# ArduinoLFO_Main.net
KiCad netlist of a schematic drawn in EAGLE
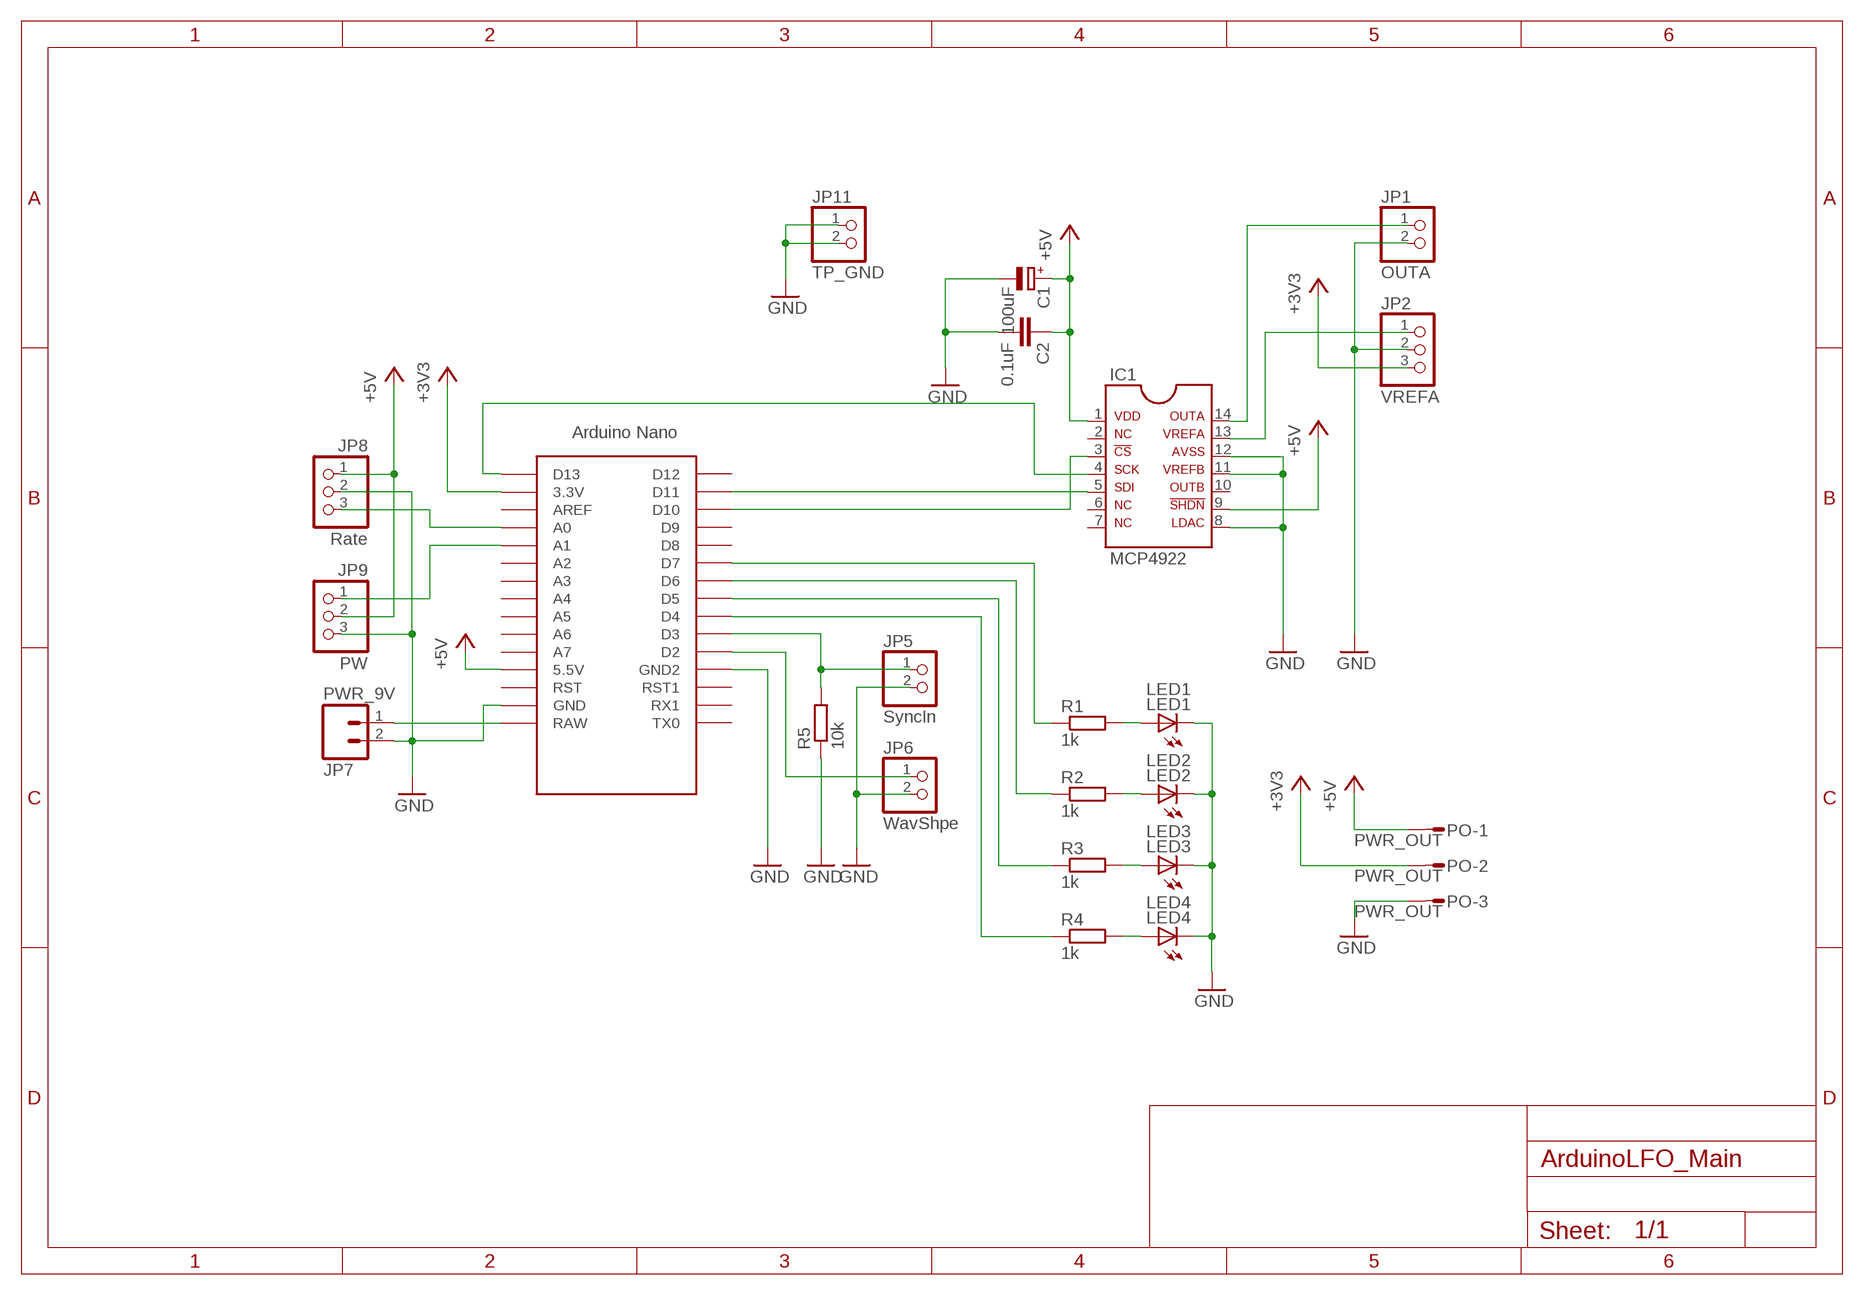
[diagram p0: schematic, sheet 1]

(export (version "E")
  (design (tool "Eeschema 10.0.6"))
  (components
    (comp (ref "C1")
      (value "100uF")
      (footprint "eagle-import:E2,5-7")
      (libsource (lib "eagle-import") (part "CPOL-EUE2.5-7"))
    )
    (comp (ref "C2")
      (value "0.1uF")
      (footprint "eagle-import:C025-024X044")
      (libsource (lib "eagle-import") (part "C-EU025-024X044"))
    )
    (comp (ref "IC1")
      (value "MCP4922")
      (footprint "eagle-import:MCP4922")
      (libsource (lib "eagle-import") (part "MCP4922"))
    )
    (comp (ref "JP1")
      (value "OUTA")
      (footprint "eagle-import:1X02")
      (libsource (lib "eagle-import") (part "PINHD-1X2"))
    )
    (comp (ref "JP2")
      (value "VREFA")
      (footprint "eagle-import:1X03")
      (libsource (lib "eagle-import") (part "PINHD-1X3"))
    )
    (comp (ref "JP5")
      (value "SyncIn")
      (footprint "eagle-import:1X02")
      (libsource (lib "eagle-import") (part "PINHD-1X2"))
    )
    (comp (ref "JP6")
      (value "WavShpe")
      (footprint "eagle-import:1X02")
      (libsource (lib "eagle-import") (part "PINHD-1X2"))
    )
    (comp (ref "JP7")
      (value "PWR_9V")
      (footprint "eagle-import:02PA")
      (libsource (lib "eagle-import") (part "MA02"))
    )
    (comp (ref "JP8")
      (value "Rate")
      (footprint "eagle-import:1X03")
      (libsource (lib "eagle-import") (part "pinhead_PINHD-1X3"))
    )
    (comp (ref "JP9")
      (value "PW")
      (footprint "eagle-import:1X03")
      (libsource (lib "eagle-import") (part "pinhead_PINHD-1X3"))
    )
    (comp (ref "JP11")
      (value "TP_GND")
      (footprint "eagle-import:1X02")
      (libsource (lib "eagle-import") (part "pinhead_PINHD-1X2"))
    )
    (comp (ref "LED1")
      (value "LED1")
      (footprint "eagle-import:LED3MM")
      (libsource (lib "eagle-import") (part "LED3MM"))
    )
    (comp (ref "LED2")
      (value "LED2")
      (footprint "eagle-import:LED3MM")
      (libsource (lib "eagle-import") (part "LED3MM"))
    )
    (comp (ref "LED3")
      (value "LED3")
      (footprint "eagle-import:LED3MM")
      (libsource (lib "eagle-import") (part "LED3MM"))
    )
    (comp (ref "LED4")
      (value "LED4")
      (footprint "eagle-import:LED3MM")
      (libsource (lib "eagle-import") (part "LED3MM"))
    )
    (comp (ref "PO")
      (value "PWR_OUT")
      (footprint "eagle-import:03PA")
      (libsource (lib "eagle-import") (part "MA03S"))
    )
    (comp (ref "R1")
      (value "1k")
      (footprint "eagle-import:0204V")
      (libsource (lib "eagle-import") (part "R-EU_0204/2V"))
    )
    (comp (ref "R2")
      (value "1k")
      (footprint "eagle-import:0204V")
      (libsource (lib "eagle-import") (part "R-EU_0204/2V"))
    )
    (comp (ref "R3")
      (value "1k")
      (footprint "eagle-import:0204V")
      (libsource (lib "eagle-import") (part "R-EU_0204/2V"))
    )
    (comp (ref "R4")
      (value "1k")
      (footprint "eagle-import:0204V")
      (libsource (lib "eagle-import") (part "R-EU_0204/2V"))
    )
    (comp (ref "R5")
      (value "10k")
      (footprint "eagle-import:0207_7")
      (libsource (lib "eagle-import") (part "R-EU_0207/7"))
    )
    (comp (ref "U$1")
      (value "NANO")
      (footprint "eagle-import:NANO")
      (libsource (lib "eagle-import") (part "NANO"))
    )
  )
  (nets
    (net (code "1") (name "+3V3") (class "Default")
      (node (ref "JP2") (pin "3") (pinfunction "3_3") (pintype "passive"))
      (node (ref "PO") (pin "2") (pinfunction "S_2") (pintype "passive"))
      (node (ref "U$1") (pin "3.3V") (pinfunction "3.3V_3.3V") (pintype "bidirectional"))
    )
    (net (code "2") (name "+5V") (class "Default")
      (node (ref "C1") (pin "+") (pinfunction "+_+") (pintype "passive"))
      (node (ref "C2") (pin "1") (pinfunction "1_1") (pintype "passive"))
      (node (ref "IC1") (pin "1") (pinfunction "1_1") (pintype "power_in"))
      (node (ref "IC1") (pin "9") (pinfunction "9_9") (pintype "input"))
      (node (ref "JP8") (pin "1") (pinfunction "1_1") (pintype "passive"))
      (node (ref "JP9") (pin "2") (pinfunction "2_2") (pintype "passive"))
      (node (ref "PO") (pin "1") (pinfunction "S_1") (pintype "passive"))
      (node (ref "U$1") (pin "5V") (pinfunction "5.5V_5V") (pintype "bidirectional"))
    )
    (net (code "3") (name "GND") (class "Default")
      (node (ref "C1") (pin "-") (pinfunction "-_-") (pintype "passive"))
      (node (ref "C2") (pin "2") (pinfunction "2_2") (pintype "passive"))
      (node (ref "IC1") (pin "11") (pinfunction "11_11") (pintype "input"))
      (node (ref "IC1") (pin "12") (pinfunction "12_12") (pintype "power_in"))
      (node (ref "IC1") (pin "8") (pinfunction "8_8") (pintype "input"))
      (node (ref "JP1") (pin "2") (pinfunction "2_2") (pintype "passive"))
      (node (ref "JP11") (pin "1") (pinfunction "1_1") (pintype "passive"))
      (node (ref "JP11") (pin "2") (pinfunction "2_2") (pintype "passive"))
      (node (ref "JP2") (pin "2") (pinfunction "2_2") (pintype "passive"))
      (node (ref "JP5") (pin "2") (pinfunction "2_2") (pintype "passive"))
      (node (ref "JP6") (pin "2") (pinfunction "2_2") (pintype "passive"))
      (node (ref "JP7") (pin "2") (pinfunction "2_2") (pintype "passive"))
      (node (ref "JP8") (pin "2") (pinfunction "2_2") (pintype "passive"))
      (node (ref "JP9") (pin "3") (pinfunction "3_3") (pintype "passive"))
      (node (ref "LED1") (pin "K") (pinfunction "C_K") (pintype "passive"))
      (node (ref "LED2") (pin "K") (pinfunction "C_K") (pintype "passive"))
      (node (ref "LED3") (pin "K") (pinfunction "C_K") (pintype "passive"))
      (node (ref "LED4") (pin "K") (pinfunction "C_K") (pintype "passive"))
      (node (ref "PO") (pin "3") (pinfunction "S_3") (pintype "passive"))
      (node (ref "R5") (pin "1") (pinfunction "1_1") (pintype "passive"))
      (node (ref "U$1") (pin "GND") (pinfunction "GND_GND") (pintype "bidirectional"))
      (node (ref "U$1") (pin "GND1") (pinfunction "GND2_GND1") (pintype "bidirectional"))
    )
    (net (code "4") (name "Net-(IC1-Pad3)") (class "Default")
      (node (ref "IC1") (pin "3") (pinfunction "3_3") (pintype "input"))
      (node (ref "U$1") (pin "D10") (pinfunction "D10_D10") (pintype "bidirectional"))
    )
    (net (code "5") (name "Net-(IC1-Pad4)") (class "Default")
      (node (ref "IC1") (pin "4") (pinfunction "4_4") (pintype "input"))
      (node (ref "U$1") (pin "D13") (pinfunction "D13_D13") (pintype "bidirectional"))
    )
    (net (code "6") (name "Net-(IC1-Pad5)") (class "Default")
      (node (ref "IC1") (pin "5") (pinfunction "5_5") (pintype "input"))
      (node (ref "U$1") (pin "D11") (pinfunction "D11_D11") (pintype "bidirectional"))
    )
    (net (code "7") (name "Net-(IC1-Pad13)") (class "Default")
      (node (ref "IC1") (pin "13") (pinfunction "13_13") (pintype "input"))
      (node (ref "JP2") (pin "1") (pinfunction "1_1") (pintype "passive"))
    )
    (net (code "8") (name "Net-(IC1-Pad14)") (class "Default")
      (node (ref "IC1") (pin "14") (pinfunction "14_14") (pintype "output"))
      (node (ref "JP1") (pin "1") (pinfunction "1_1") (pintype "passive"))
    )
    (net (code "9") (name "Net-(JP5-Pad1)") (class "Default")
      (node (ref "JP5") (pin "1") (pinfunction "1_1") (pintype "passive"))
      (node (ref "R5") (pin "2") (pinfunction "2_2") (pintype "passive"))
      (node (ref "U$1") (pin "D3") (pinfunction "D3_D3") (pintype "bidirectional"))
    )
    (net (code "10") (name "Net-(JP6-Pad1)") (class "Default")
      (node (ref "JP6") (pin "1") (pinfunction "1_1") (pintype "passive"))
      (node (ref "U$1") (pin "D2") (pinfunction "D2_D2") (pintype "bidirectional"))
    )
    (net (code "11") (name "Net-(JP7-Pad1)") (class "Default")
      (node (ref "JP7") (pin "1") (pinfunction "1_1") (pintype "passive"))
      (node (ref "U$1") (pin "RAW") (pinfunction "RAW_RAW") (pintype "bidirectional"))
    )
    (net (code "12") (name "Net-(JP8-Pad3)") (class "Default")
      (node (ref "JP8") (pin "3") (pinfunction "3_3") (pintype "passive"))
      (node (ref "U$1") (pin "A0") (pinfunction "A0_A0") (pintype "bidirectional"))
    )
    (net (code "13") (name "Net-(JP9-Pad1)") (class "Default")
      (node (ref "JP9") (pin "1") (pinfunction "1_1") (pintype "passive"))
      (node (ref "U$1") (pin "A1") (pinfunction "A1_A1") (pintype "bidirectional"))
    )
    (net (code "14") (name "Net-(LED1-PadA)") (class "Default")
      (node (ref "LED1") (pin "A") (pinfunction "A_A") (pintype "passive"))
      (node (ref "R1") (pin "2") (pinfunction "2_2") (pintype "passive"))
    )
    (net (code "15") (name "Net-(LED2-PadA)") (class "Default")
      (node (ref "LED2") (pin "A") (pinfunction "A_A") (pintype "passive"))
      (node (ref "R2") (pin "2") (pinfunction "2_2") (pintype "passive"))
    )
    (net (code "16") (name "Net-(LED3-PadA)") (class "Default")
      (node (ref "LED3") (pin "A") (pinfunction "A_A") (pintype "passive"))
      (node (ref "R3") (pin "2") (pinfunction "2_2") (pintype "passive"))
    )
    (net (code "17") (name "Net-(LED4-PadA)") (class "Default")
      (node (ref "LED4") (pin "A") (pinfunction "A_A") (pintype "passive"))
      (node (ref "R4") (pin "2") (pinfunction "2_2") (pintype "passive"))
    )
    (net (code "18") (name "Net-(R1-Pad1)") (class "Default")
      (node (ref "R1") (pin "1") (pinfunction "1_1") (pintype "passive"))
      (node (ref "U$1") (pin "D7") (pinfunction "D7_D7") (pintype "bidirectional"))
    )
    (net (code "19") (name "Net-(R2-Pad1)") (class "Default")
      (node (ref "R2") (pin "1") (pinfunction "1_1") (pintype "passive"))
      (node (ref "U$1") (pin "D6") (pinfunction "D6_D6") (pintype "bidirectional"))
    )
    (net (code "20") (name "Net-(R3-Pad1)") (class "Default")
      (node (ref "R3") (pin "1") (pinfunction "1_1") (pintype "passive"))
      (node (ref "U$1") (pin "D5") (pinfunction "D5_D5") (pintype "bidirectional"))
    )
    (net (code "21") (name "Net-(R4-Pad1)") (class "Default")
      (node (ref "R4") (pin "1") (pinfunction "1_1") (pintype "passive"))
      (node (ref "U$1") (pin "D4") (pinfunction "D4_D4") (pintype "bidirectional"))
    )
    (net (code "22") (name "unconnected-(IC1-Pad2)") (class "Default")
      (node (ref "IC1") (pin "2") (pinfunction "2_2") (pintype "no_connect"))
    )
    (net (code "23") (name "unconnected-(IC1-Pad6)") (class "Default")
      (node (ref "IC1") (pin "6") (pinfunction "6_6") (pintype "no_connect"))
    )
    (net (code "24") (name "unconnected-(IC1-Pad7)") (class "Default")
      (node (ref "IC1") (pin "7") (pinfunction "7_7") (pintype "no_connect"))
    )
    (net (code "25") (name "unconnected-(IC1-Pad10)") (class "Default")
      (node (ref "IC1") (pin "10") (pinfunction "10_10") (pintype "output"))
    )
    (net (code "26") (name "unconnected-(U$1-PadA2)") (class "Default")
      (node (ref "U$1") (pin "A2") (pinfunction "A2_A2") (pintype "bidirectional"))
    )
    (net (code "27") (name "unconnected-(U$1-PadA3)") (class "Default")
      (node (ref "U$1") (pin "A3") (pinfunction "A3_A3") (pintype "bidirectional"))
    )
    (net (code "28") (name "unconnected-(U$1-PadA4)") (class "Default")
      (node (ref "U$1") (pin "A4") (pinfunction "A4_A4") (pintype "bidirectional"))
    )
    (net (code "29") (name "unconnected-(U$1-PadA5)") (class "Default")
      (node (ref "U$1") (pin "A5") (pinfunction "A5_A5") (pintype "bidirectional"))
    )
    (net (code "30") (name "unconnected-(U$1-PadA6)") (class "Default")
      (node (ref "U$1") (pin "A6") (pinfunction "A6_A6") (pintype "bidirectional"))
    )
    (net (code "31") (name "unconnected-(U$1-PadA7)") (class "Default")
      (node (ref "U$1") (pin "A7") (pinfunction "A7_A7") (pintype "bidirectional"))
    )
    (net (code "32") (name "unconnected-(U$1-PadAREF)") (class "Default")
      (node (ref "U$1") (pin "AREF") (pinfunction "AREF_AREF") (pintype "bidirectional"))
    )
    (net (code "33") (name "unconnected-(U$1-PadD8)") (class "Default")
      (node (ref "U$1") (pin "D8") (pinfunction "D8_D8") (pintype "bidirectional"))
    )
    (net (code "34") (name "unconnected-(U$1-PadD9)") (class "Default")
      (node (ref "U$1") (pin "D9") (pinfunction "D9_D9") (pintype "bidirectional"))
    )
    (net (code "35") (name "unconnected-(U$1-PadD12)") (class "Default")
      (node (ref "U$1") (pin "D12") (pinfunction "D12_D12") (pintype "bidirectional"))
    )
    (net (code "36") (name "unconnected-(U$1-PadICSP1)") (class "Default")
      (node (ref "U$1") (pin "ICSP1") (pinfunction "ICSP1_ICSP1") (pintype "bidirectional"))
    )
    (net (code "37") (name "unconnected-(U$1-PadICSP2)") (class "Default")
      (node (ref "U$1") (pin "ICSP2") (pinfunction "ICSP2_ICSP2") (pintype "bidirectional"))
    )
    (net (code "38") (name "unconnected-(U$1-PadICSP3)") (class "Default")
      (node (ref "U$1") (pin "ICSP3") (pinfunction "ICSP3_ICSP3") (pintype "bidirectional"))
    )
    (net (code "39") (name "unconnected-(U$1-PadICSP4)") (class "Default")
      (node (ref "U$1") (pin "ICSP4") (pinfunction "ICSP4_ICSP4") (pintype "bidirectional"))
    )
    (net (code "40") (name "unconnected-(U$1-PadICSP5)") (class "Default")
      (node (ref "U$1") (pin "ICSP5") (pinfunction "ICSP5_ICSP5") (pintype "bidirectional"))
    )
    (net (code "41") (name "unconnected-(U$1-PadICSP6)") (class "Default")
      (node (ref "U$1") (pin "ICSP6") (pinfunction "ICSP6_ICSP6") (pintype "bidirectional"))
    )
    (net (code "42") (name "unconnected-(U$1-PadRST)") (class "Default")
      (node (ref "U$1") (pin "RST") (pinfunction "RST_RST") (pintype "bidirectional"))
    )
    (net (code "43") (name "unconnected-(U$1-PadRST1)") (class "Default")
      (node (ref "U$1") (pin "RST1") (pinfunction "RST1_RST1") (pintype "bidirectional"))
    )
    (net (code "44") (name "unconnected-(U$1-PadRX1)") (class "Default")
      (node (ref "U$1") (pin "RX1") (pinfunction "RX1_RX1") (pintype "bidirectional"))
    )
    (net (code "45") (name "unconnected-(U$1-PadTX0)") (class "Default")
      (node (ref "U$1") (pin "TX0") (pinfunction "TX0_TX0") (pintype "bidirectional"))
    )
  )
)
